# brushed_motor_drivers.net
KiCad netlist of a schematic drawn in Altium Designer
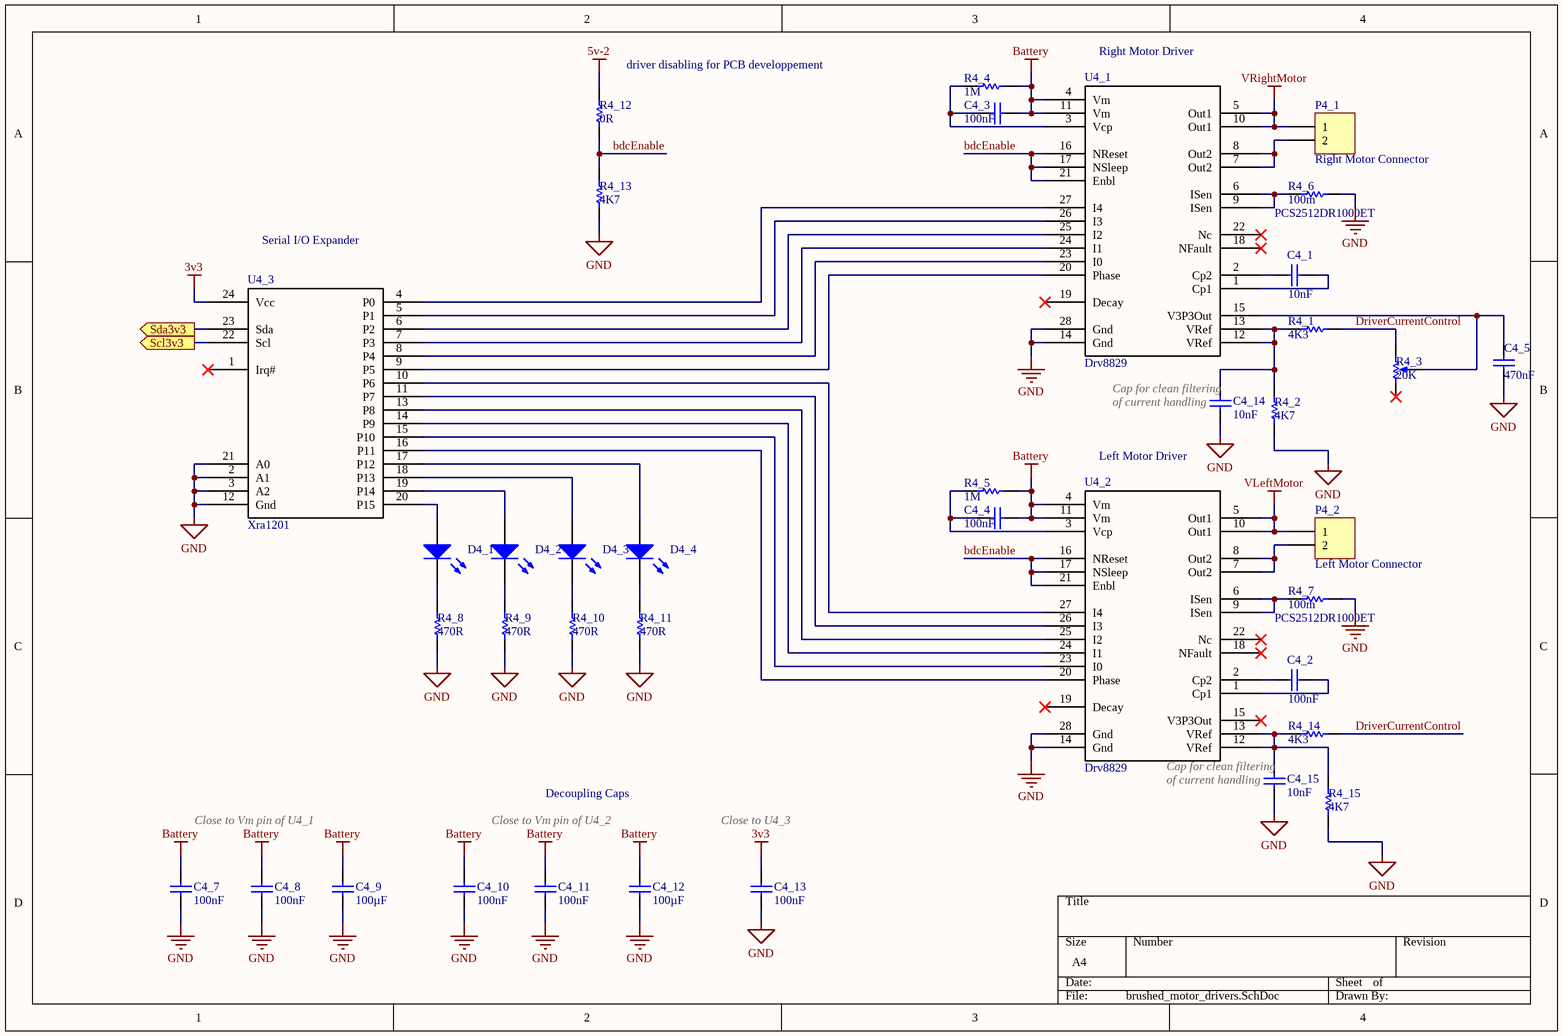
[diagram p0: brushed_motor_drivers.SchDoc]

(export (version "E")
  (design (tool "Eeschema 10.0.6"))
  (components
    (comp (ref "C4_1")
      (value "10nF")
      (footprint "C1206")
      (description "Capacitor")
      (fields (field (name "Comment") "C1206C103M5RACTU") (field (name "PUBLISHER") "Altium Limited"))
      (libsource (lib "Miscellaneous Devices") (part "Cap"))
    )
    (comp (ref "C4_2")
      (value "100nF")
      (footprint "C1206")
      (description "Capacitor")
      (fields (field (name "Comment") "C1206C103M5RACTU") (field (name "PUBLISHER") "Altium Limited"))
      (libsource (lib "Miscellaneous Devices") (part "Cap"))
    )
    (comp (ref "C4_3")
      (value "100nF")
      (footprint "C1206")
      (description "Capacitor")
      (fields (field (name "Comment") "12063C104MAT2A") (field (name "PUBLISHER") "Altium Limited"))
      (libsource (lib "Miscellaneous Devices") (part "Cap"))
    )
    (comp (ref "C4_4")
      (value "100nF")
      (footprint "C1206")
      (description "Capacitor")
      (fields (field (name "Comment") "12063C104MAT2A") (field (name "PUBLISHER") "Altium Limited"))
      (libsource (lib "Miscellaneous Devices") (part "Cap"))
    )
    (comp (ref "C4_5")
      (value "470nF")
      (footprint "C1206")
      (description "Capacitor")
      (fields (field (name "Comment") "C1206C474M5RECAUTO") (field (name "PUBLISHER") "Altium Limited"))
      (libsource (lib "Miscellaneous Devices") (part "Cap"))
    )
    (comp (ref "C4_7")
      (value "100nF")
      (footprint "C1206")
      (description "Capacitor")
      (fields (field (name "Comment") "12063C104MAT2A") (field (name "PUBLISHER") "Altium Limited"))
      (libsource (lib "Miscellaneous Devices") (part "Cap"))
    )
    (comp (ref "C4_8")
      (value "100nF")
      (footprint "C1206")
      (description "Capacitor")
      (fields (field (name "Comment") "12063C104MAT2A") (field (name "PUBLISHER") "Altium Limited"))
      (libsource (lib "Miscellaneous Devices") (part "Cap"))
    )
    (comp (ref "C4_9")
      (value "100µF")
      (footprint "CAP-ELECTRO-530530")
      (description "Capacitor")
      (fields (field (name "Comment") "107AXZ016MQ5") (field (name "PUBLISHER") "Altium Limited"))
      (libsource (lib "Miscellaneous Devices") (part "Cap"))
    )
    (comp (ref "C4_10")
      (value "100nF")
      (footprint "C1206")
      (description "Capacitor")
      (fields (field (name "Comment") "12063C104MAT2A") (field (name "PUBLISHER") "Altium Limited"))
      (libsource (lib "Miscellaneous Devices") (part "Cap"))
    )
    (comp (ref "C4_11")
      (value "100nF")
      (footprint "C1206")
      (description "Capacitor")
      (fields (field (name "Comment") "12063C104MAT2A") (field (name "PUBLISHER") "Altium Limited"))
      (libsource (lib "Miscellaneous Devices") (part "Cap"))
    )
    (comp (ref "C4_12")
      (value "100µF")
      (footprint "CAP-ELECTRO-530530")
      (description "Capacitor")
      (fields (field (name "Comment") "107AXZ016MQ5") (field (name "PUBLISHER") "Altium Limited"))
      (libsource (lib "Miscellaneous Devices") (part "Cap"))
    )
    (comp (ref "C4_13")
      (value "100nF")
      (footprint "C1206")
      (description "Capacitor")
      (fields (field (name "Comment") "12063C104MAT2A") (field (name "PUBLISHER") "Altium Limited"))
      (libsource (lib "Miscellaneous Devices") (part "Cap"))
    )
    (comp (ref "C4_14")
      (value "10nF")
      (footprint "C1206")
      (description "Capacitor")
      (fields (field (name "Comment") "C1206C103M5RACTU") (field (name "PUBLISHER") "Altium Limited"))
      (libsource (lib "Miscellaneous Devices") (part "Cap"))
    )
    (comp (ref "C4_15")
      (value "10nF")
      (footprint "C1206")
      (description "Capacitor")
      (fields (field (name "Comment") "C1206C103M5RACTU") (field (name "PUBLISHER") "Altium Limited"))
      (libsource (lib "Miscellaneous Devices") (part "Cap"))
    )
    (comp (ref "D4_1")
      (value "APT3216QBC/D")
      (footprint "C1206-POLARIZED")
      (description "Typical INFRARED GaAs LED")
      (fields (field (name "PUBLISHER") "Altium Limited"))
      (libsource (lib "Miscellaneous Devices") (part "LED0"))
    )
    (comp (ref "D4_2")
      (value "APT3216QBC/D")
      (footprint "C1206-POLARIZED")
      (description "Typical INFRARED GaAs LED")
      (fields (field (name "PUBLISHER") "Altium Limited"))
      (libsource (lib "Miscellaneous Devices") (part "LED0"))
    )
    (comp (ref "D4_3")
      (value "APT3216QBC/D")
      (footprint "C1206-POLARIZED")
      (description "Typical INFRARED GaAs LED")
      (fields (field (name "PUBLISHER") "Altium Limited"))
      (libsource (lib "Miscellaneous Devices") (part "LED0"))
    )
    (comp (ref "D4_4")
      (value "APT3216QBC/D")
      (footprint "C1206-POLARIZED")
      (description "Typical INFRARED GaAs LED")
      (fields (field (name "PUBLISHER") "Altium Limited"))
      (libsource (lib "Miscellaneous Devices") (part "LED0"))
    )
    (comp (ref "P4_1")
      (value "Right Motor Connector")
      (footprint "HDR1X2-42")
      (description "Header, 2-Pin")
      (fields (field (name "PUBLISHER") "Altium Limited"))
      (libsource (lib "Miscellaneous Connectors") (part "Header 2"))
    )
    (comp (ref "P4_2")
      (value "Left Motor Connector")
      (footprint "HDR1X2-42")
      (description "Header, 2-Pin")
      (fields (field (name "PUBLISHER") "Altium Limited"))
      (libsource (lib "Miscellaneous Connectors") (part "Header 2"))
    )
    (comp (ref "R4_1")
      (value "4K3")
      (footprint "C1206")
      (description "Resistor")
      (fields (field (name "Comment") "Res1") (field (name "PUBLISHER") "Altium Limited"))
      (libsource (lib "Miscellaneous Devices") (part "Res1"))
    )
    (comp (ref "R4_2")
      (value "4K7")
      (footprint "C1206")
      (description "Resistor")
      (fields (field (name "Comment") "Res1") (field (name "PUBLISHER") "Altium Limited"))
      (libsource (lib "Miscellaneous Devices") (part "Res1"))
    )
    (comp (ref "R4_3")
      (value "20K")
      (footprint "ST-32EB")
      (description "Potentiometer")
      (fields (field (name "Comment") "ST32ETB203") (field (name "PUBLISHER") "Altium Limited"))
      (libsource (lib "Miscellaneous Devices") (part "RPot"))
    )
    (comp (ref "R4_4")
      (value "1M")
      (footprint "C1206")
      (description "Resistor")
      (fields (field (name "Comment") "Res1") (field (name "PUBLISHER") "Altium Limited"))
      (libsource (lib "Miscellaneous Devices") (part "Res1"))
    )
    (comp (ref "R4_5")
      (value "1M")
      (footprint "C1206")
      (description "Resistor")
      (fields (field (name "Comment") "Res1") (field (name "PUBLISHER") "Altium Limited"))
      (libsource (lib "Miscellaneous Devices") (part "Res1"))
    )
    (comp (ref "R4_6")
      (value "PCS2512DR1000ET")
      (footprint "2512")
      (description "Resistor")
      (fields (field (name "ALTIUM_VALUE") "100m") (field (name "PUBLISHER") "Altium Limited"))
      (libsource (lib "Miscellaneous Devices") (part "Res1"))
    )
    (comp (ref "R4_7")
      (value "PCS2512DR1000ET")
      (footprint "2512")
      (description "Resistor")
      (fields (field (name "ALTIUM_VALUE") "100m") (field (name "PUBLISHER") "Altium Limited"))
      (libsource (lib "Miscellaneous Devices") (part "Res1"))
    )
    (comp (ref "R4_8")
      (value "470R")
      (footprint "C1206")
      (description "Resistor")
      (fields (field (name "Comment") "Res1") (field (name "PUBLISHER") "Altium Limited"))
      (libsource (lib "Miscellaneous Devices") (part "Res1"))
    )
    (comp (ref "R4_9")
      (value "470R")
      (footprint "C1206")
      (description "Resistor")
      (fields (field (name "Comment") "Res1") (field (name "PUBLISHER") "Altium Limited"))
      (libsource (lib "Miscellaneous Devices") (part "Res1"))
    )
    (comp (ref "R4_10")
      (value "470R")
      (footprint "C1206")
      (description "Resistor")
      (fields (field (name "Comment") "Res1") (field (name "PUBLISHER") "Altium Limited"))
      (libsource (lib "Miscellaneous Devices") (part "Res1"))
    )
    (comp (ref "R4_11")
      (value "470R")
      (footprint "C1206")
      (description "Resistor")
      (fields (field (name "Comment") "Res1") (field (name "PUBLISHER") "Altium Limited"))
      (libsource (lib "Miscellaneous Devices") (part "Res1"))
    )
    (comp (ref "R4_12")
      (value "0R")
      (footprint "C0805")
      (description "Resistor")
      (fields (field (name "Comment") "Res1") (field (name "PUBLISHER") "Altium Limited"))
      (libsource (lib "Miscellaneous Devices") (part "Res1"))
    )
    (comp (ref "R4_13")
      (value "4K7")
      (footprint "C1206")
      (description "Resistor")
      (fields (field (name "Comment") "Res1") (field (name "PUBLISHER") "Altium Limited"))
      (libsource (lib "Miscellaneous Devices") (part "Res1"))
    )
    (comp (ref "R4_14")
      (value "4K3")
      (footprint "C1206")
      (description "Resistor")
      (fields (field (name "Comment") "Res1") (field (name "PUBLISHER") "Altium Limited"))
      (libsource (lib "Miscellaneous Devices") (part "Res1"))
    )
    (comp (ref "R4_15")
      (value "4K7")
      (footprint "C1206")
      (description "Resistor")
      (fields (field (name "Comment") "Res1") (field (name "PUBLISHER") "Altium Limited"))
      (libsource (lib "Miscellaneous Devices") (part "Res1"))
    )
    (comp (ref "U4_1")
      (value "Drv8829")
      (footprint "SOP65P640X120-28N-GROUND_SINK")
      (libsource (lib "projet 6e session") (part "Drv8829"))
    )
    (comp (ref "U4_2")
      (value "Drv8829")
      (footprint "SOP65P640X120-28N-GROUND_SINK")
      (libsource (lib "projet 6e session") (part "Drv8829"))
    )
    (comp (ref "U4_3")
      (value "Xra1201")
      (footprint "SOP65P640X110-24N")
      (libsource (lib "projet 6e session") (part "Xra1201"))
    )
  )
  (nets
    (net (code "1") (name "/DriverCurrentControl") (class "Default")
      (node (ref "R4_1") (pin "2") (pinfunction "2_2") (pintype "passive"))
      (node (ref "R4_14") (pin "2") (pinfunction "2_2") (pintype "passive"))
      (node (ref "R4_3") (pin "2") (pinfunction "BOT_2") (pintype "passive"))
    )
    (net (code "2") (name "/Scl3v3") (class "Default")
      (node (ref "U4_3") (pin "22") (pinfunction "Scl_22") (pintype "passive"))
    )
    (net (code "3") (name "/Sda3v3") (class "Default")
      (node (ref "U4_3") (pin "23") (pinfunction "Sda_23") (pintype "passive"))
    )
    (net (code "4") (name "/bdcEnable") (class "Default")
      (node (ref "R4_12") (pin "2") (pinfunction "2_2") (pintype "passive"))
      (node (ref "R4_13") (pin "1") (pinfunction "1_1") (pintype "passive"))
      (node (ref "U4_1") (pin "16") (pinfunction "NReset_16") (pintype "passive"))
      (node (ref "U4_1") (pin "17") (pinfunction "NSleep_17") (pintype "passive"))
      (node (ref "U4_1") (pin "21") (pinfunction "Enbl_21") (pintype "passive"))
      (node (ref "U4_2") (pin "16") (pinfunction "NReset_16") (pintype "passive"))
      (node (ref "U4_2") (pin "17") (pinfunction "NSleep_17") (pintype "passive"))
      (node (ref "U4_2") (pin "21") (pinfunction "Enbl_21") (pintype "passive"))
    )
    (net (code "5") (name "3v3") (class "Default")
      (node (ref "C4_13") (pin "1") (pinfunction "1_1") (pintype "passive"))
      (node (ref "U4_3") (pin "24") (pinfunction "Vcc_24") (pintype "passive"))
    )
    (net (code "6") (name "5v-2") (class "Default")
      (node (ref "R4_12") (pin "1") (pinfunction "1_1") (pintype "passive"))
    )
    (net (code "7") (name "Battery") (class "Default")
      (node (ref "C4_10") (pin "1") (pinfunction "1_1") (pintype "passive"))
      (node (ref "C4_11") (pin "1") (pinfunction "1_1") (pintype "passive"))
      (node (ref "C4_12") (pin "1") (pinfunction "1_1") (pintype "passive"))
      (node (ref "C4_3") (pin "1") (pinfunction "1_1") (pintype "passive"))
      (node (ref "C4_4") (pin "1") (pinfunction "1_1") (pintype "passive"))
      (node (ref "C4_7") (pin "1") (pinfunction "1_1") (pintype "passive"))
      (node (ref "C4_8") (pin "1") (pinfunction "1_1") (pintype "passive"))
      (node (ref "C4_9") (pin "1") (pinfunction "1_1") (pintype "passive"))
      (node (ref "R4_4") (pin "2") (pinfunction "2_2") (pintype "passive"))
      (node (ref "R4_5") (pin "2") (pinfunction "2_2") (pintype "passive"))
      (node (ref "U4_1") (pin "11") (pinfunction "Vm_11") (pintype "passive"))
      (node (ref "U4_1") (pin "4") (pinfunction "Vm_4") (pintype "passive"))
      (node (ref "U4_2") (pin "11") (pinfunction "Vm_11") (pintype "passive"))
      (node (ref "U4_2") (pin "4") (pinfunction "Vm_4") (pintype "passive"))
    )
    (net (code "8") (name "GND") (class "Default")
      (node (ref "C4_10") (pin "2") (pinfunction "2_2") (pintype "passive"))
      (node (ref "C4_11") (pin "2") (pinfunction "2_2") (pintype "passive"))
      (node (ref "C4_12") (pin "2") (pinfunction "2_2") (pintype "passive"))
      (node (ref "C4_13") (pin "2") (pinfunction "2_2") (pintype "passive"))
      (node (ref "C4_14") (pin "2") (pinfunction "2_2") (pintype "passive"))
      (node (ref "C4_15") (pin "2") (pinfunction "2_2") (pintype "passive"))
      (node (ref "C4_5") (pin "2") (pinfunction "2_2") (pintype "passive"))
      (node (ref "C4_7") (pin "2") (pinfunction "2_2") (pintype "passive"))
      (node (ref "C4_8") (pin "2") (pinfunction "2_2") (pintype "passive"))
      (node (ref "C4_9") (pin "2") (pinfunction "2_2") (pintype "passive"))
      (node (ref "R4_10") (pin "2") (pinfunction "2_2") (pintype "passive"))
      (node (ref "R4_11") (pin "2") (pinfunction "2_2") (pintype "passive"))
      (node (ref "R4_13") (pin "2") (pinfunction "2_2") (pintype "passive"))
      (node (ref "R4_15") (pin "2") (pinfunction "2_2") (pintype "passive"))
      (node (ref "R4_2") (pin "2") (pinfunction "2_2") (pintype "passive"))
      (node (ref "R4_6") (pin "2") (pinfunction "2_2") (pintype "passive"))
      (node (ref "R4_7") (pin "2") (pinfunction "2_2") (pintype "passive"))
      (node (ref "R4_8") (pin "2") (pinfunction "2_2") (pintype "passive"))
      (node (ref "R4_9") (pin "2") (pinfunction "2_2") (pintype "passive"))
      (node (ref "U4_1") (pin "14") (pinfunction "Gnd_14") (pintype "passive"))
      (node (ref "U4_1") (pin "28") (pinfunction "Gnd_28") (pintype "passive"))
      (node (ref "U4_2") (pin "14") (pinfunction "Gnd_14") (pintype "passive"))
      (node (ref "U4_2") (pin "28") (pinfunction "Gnd_28") (pintype "passive"))
      (node (ref "U4_3") (pin "12") (pinfunction "Gnd_12") (pintype "passive"))
      (node (ref "U4_3") (pin "2") (pinfunction "A1_2") (pintype "passive"))
      (node (ref "U4_3") (pin "21") (pinfunction "A0_21") (pintype "passive"))
      (node (ref "U4_3") (pin "3") (pinfunction "A2_3") (pintype "passive"))
    )
    (net (code "9") (name "Net-(C4_14-Pad1)") (class "Default")
      (node (ref "C4_14") (pin "1") (pinfunction "1_1") (pintype "passive"))
      (node (ref "R4_1") (pin "1") (pinfunction "1_1") (pintype "passive"))
      (node (ref "R4_2") (pin "1") (pinfunction "1_1") (pintype "passive"))
      (node (ref "U4_1") (pin "12") (pinfunction "VRef_12") (pintype "passive"))
      (node (ref "U4_1") (pin "13") (pinfunction "VRef_13") (pintype "passive"))
    )
    (net (code "10") (name "Net-(C4_15-Pad1)") (class "Default")
      (node (ref "C4_15") (pin "1") (pinfunction "1_1") (pintype "passive"))
      (node (ref "R4_14") (pin "1") (pinfunction "1_1") (pintype "passive"))
      (node (ref "R4_15") (pin "1") (pinfunction "1_1") (pintype "passive"))
      (node (ref "U4_2") (pin "12") (pinfunction "VRef_12") (pintype "passive"))
      (node (ref "U4_2") (pin "13") (pinfunction "VRef_13") (pintype "passive"))
    )
    (net (code "11") (name "Net-(D4_1-A)") (class "Default")
      (node (ref "D4_1") (pin "1") (pinfunction "A_1") (pintype "passive"))
      (node (ref "U4_3") (pin "20") (pinfunction "P15_20") (pintype "passive"))
    )
    (net (code "12") (name "Net-(D4_1-K)") (class "Default")
      (node (ref "D4_1") (pin "2") (pinfunction "K_2") (pintype "passive"))
      (node (ref "R4_8") (pin "1") (pinfunction "1_1") (pintype "passive"))
    )
    (net (code "13") (name "Net-(D4_2-A)") (class "Default")
      (node (ref "D4_2") (pin "1") (pinfunction "A_1") (pintype "passive"))
      (node (ref "U4_3") (pin "19") (pinfunction "P14_19") (pintype "passive"))
    )
    (net (code "14") (name "Net-(D4_2-K)") (class "Default")
      (node (ref "D4_2") (pin "2") (pinfunction "K_2") (pintype "passive"))
      (node (ref "R4_9") (pin "1") (pinfunction "1_1") (pintype "passive"))
    )
    (net (code "15") (name "Net-(D4_3-A)") (class "Default")
      (node (ref "D4_3") (pin "1") (pinfunction "A_1") (pintype "passive"))
      (node (ref "U4_3") (pin "18") (pinfunction "P13_18") (pintype "passive"))
    )
    (net (code "16") (name "Net-(D4_3-K)") (class "Default")
      (node (ref "D4_3") (pin "2") (pinfunction "K_2") (pintype "passive"))
      (node (ref "R4_10") (pin "1") (pinfunction "1_1") (pintype "passive"))
    )
    (net (code "17") (name "Net-(D4_4-A)") (class "Default")
      (node (ref "D4_4") (pin "1") (pinfunction "A_1") (pintype "passive"))
      (node (ref "U4_3") (pin "17") (pinfunction "P12_17") (pintype "passive"))
    )
    (net (code "18") (name "Net-(D4_4-K)") (class "Default")
      (node (ref "D4_4") (pin "2") (pinfunction "K_2") (pintype "passive"))
      (node (ref "R4_11") (pin "1") (pinfunction "1_1") (pintype "passive"))
    )
    (net (code "19") (name "Net-(P4_1-Pad2)") (class "Default")
      (node (ref "P4_1") (pin "2") (pinfunction "2_2") (pintype "passive"))
      (node (ref "U4_1") (pin "7") (pinfunction "Out2_7") (pintype "passive"))
      (node (ref "U4_1") (pin "8") (pinfunction "Out2_8") (pintype "passive"))
    )
    (net (code "20") (name "Net-(P4_2-Pad2)") (class "Default")
      (node (ref "P4_2") (pin "2") (pinfunction "2_2") (pintype "passive"))
      (node (ref "U4_2") (pin "7") (pinfunction "Out2_7") (pintype "passive"))
      (node (ref "U4_2") (pin "8") (pinfunction "Out2_8") (pintype "passive"))
    )
    (net (code "21") (name "Net-(R4_3-TAP)") (class "Default")
      (node (ref "C4_5") (pin "1") (pinfunction "1_1") (pintype "passive"))
      (node (ref "R4_3") (pin "3") (pinfunction "TAP_3") (pintype "passive"))
      (node (ref "U4_1") (pin "15") (pinfunction "V3P3Out_15") (pintype "passive"))
    )
    (net (code "22") (name "Net-(R4_6-Pad1)") (class "Default")
      (node (ref "R4_6") (pin "1") (pinfunction "1_1") (pintype "passive"))
      (node (ref "U4_1") (pin "6") (pinfunction "ISen_6") (pintype "passive"))
      (node (ref "U4_1") (pin "9") (pinfunction "ISen_9") (pintype "passive"))
    )
    (net (code "23") (name "Net-(R4_7-Pad1)") (class "Default")
      (node (ref "R4_7") (pin "1") (pinfunction "1_1") (pintype "passive"))
      (node (ref "U4_2") (pin "6") (pinfunction "ISen_6") (pintype "passive"))
      (node (ref "U4_2") (pin "9") (pinfunction "ISen_9") (pintype "passive"))
    )
    (net (code "24") (name "Net-(U4_1-Cp1)") (class "Default")
      (node (ref "C4_1") (pin "1") (pinfunction "1_1") (pintype "passive"))
      (node (ref "U4_1") (pin "1") (pinfunction "Cp1_1") (pintype "passive"))
    )
    (net (code "25") (name "Net-(U4_1-Cp2)") (class "Default")
      (node (ref "C4_1") (pin "2") (pinfunction "2_2") (pintype "passive"))
      (node (ref "U4_1") (pin "2") (pinfunction "Cp2_2") (pintype "passive"))
    )
    (net (code "26") (name "Net-(U4_1-I0)") (class "Default")
      (node (ref "U4_1") (pin "23") (pinfunction "I0_23") (pintype "passive"))
      (node (ref "U4_3") (pin "8") (pinfunction "P4_8") (pintype "passive"))
    )
    (net (code "27") (name "Net-(U4_1-I1)") (class "Default")
      (node (ref "U4_1") (pin "24") (pinfunction "I1_24") (pintype "passive"))
      (node (ref "U4_3") (pin "7") (pinfunction "P3_7") (pintype "passive"))
    )
    (net (code "28") (name "Net-(U4_1-I2)") (class "Default")
      (node (ref "U4_1") (pin "25") (pinfunction "I2_25") (pintype "passive"))
      (node (ref "U4_3") (pin "6") (pinfunction "P2_6") (pintype "passive"))
    )
    (net (code "29") (name "Net-(U4_1-I3)") (class "Default")
      (node (ref "U4_1") (pin "26") (pinfunction "I3_26") (pintype "passive"))
      (node (ref "U4_3") (pin "5") (pinfunction "P1_5") (pintype "passive"))
    )
    (net (code "30") (name "Net-(U4_1-I4)") (class "Default")
      (node (ref "U4_1") (pin "27") (pinfunction "I4_27") (pintype "passive"))
      (node (ref "U4_3") (pin "4") (pinfunction "P0_4") (pintype "passive"))
    )
    (net (code "31") (name "Net-(U4_1-Phase)") (class "Default")
      (node (ref "U4_1") (pin "20") (pinfunction "Phase_20") (pintype "passive"))
      (node (ref "U4_3") (pin "9") (pinfunction "P5_9") (pintype "passive"))
    )
    (net (code "32") (name "Net-(U4_1-Vcp)") (class "Default")
      (node (ref "C4_3") (pin "2") (pinfunction "2_2") (pintype "passive"))
      (node (ref "R4_4") (pin "1") (pinfunction "1_1") (pintype "passive"))
      (node (ref "U4_1") (pin "3") (pinfunction "Vcp_3") (pintype "passive"))
    )
    (net (code "33") (name "Net-(U4_2-Cp1)") (class "Default")
      (node (ref "C4_2") (pin "1") (pinfunction "1_1") (pintype "passive"))
      (node (ref "U4_2") (pin "1") (pinfunction "Cp1_1") (pintype "passive"))
    )
    (net (code "34") (name "Net-(U4_2-Cp2)") (class "Default")
      (node (ref "C4_2") (pin "2") (pinfunction "2_2") (pintype "passive"))
      (node (ref "U4_2") (pin "2") (pinfunction "Cp2_2") (pintype "passive"))
    )
    (net (code "35") (name "Net-(U4_2-I0)") (class "Default")
      (node (ref "U4_2") (pin "23") (pinfunction "I0_23") (pintype "passive"))
      (node (ref "U4_3") (pin "15") (pinfunction "P10_15") (pintype "passive"))
    )
    (net (code "36") (name "Net-(U4_2-I1)") (class "Default")
      (node (ref "U4_2") (pin "24") (pinfunction "I1_24") (pintype "passive"))
      (node (ref "U4_3") (pin "14") (pinfunction "P9_14") (pintype "passive"))
    )
    (net (code "37") (name "Net-(U4_2-I2)") (class "Default")
      (node (ref "U4_2") (pin "25") (pinfunction "I2_25") (pintype "passive"))
      (node (ref "U4_3") (pin "13") (pinfunction "P8_13") (pintype "passive"))
    )
    (net (code "38") (name "Net-(U4_2-I3)") (class "Default")
      (node (ref "U4_2") (pin "26") (pinfunction "I3_26") (pintype "passive"))
      (node (ref "U4_3") (pin "11") (pinfunction "P7_11") (pintype "passive"))
    )
    (net (code "39") (name "Net-(U4_2-I4)") (class "Default")
      (node (ref "U4_2") (pin "27") (pinfunction "I4_27") (pintype "passive"))
      (node (ref "U4_3") (pin "10") (pinfunction "P6_10") (pintype "passive"))
    )
    (net (code "40") (name "Net-(U4_2-Phase)") (class "Default")
      (node (ref "U4_2") (pin "20") (pinfunction "Phase_20") (pintype "passive"))
      (node (ref "U4_3") (pin "16") (pinfunction "P11_16") (pintype "passive"))
    )
    (net (code "41") (name "Net-(U4_2-Vcp)") (class "Default")
      (node (ref "C4_4") (pin "2") (pinfunction "2_2") (pintype "passive"))
      (node (ref "R4_5") (pin "1") (pinfunction "1_1") (pintype "passive"))
      (node (ref "U4_2") (pin "3") (pinfunction "Vcp_3") (pintype "passive"))
    )
    (net (code "42") (name "VLeftMotor") (class "Default")
      (node (ref "P4_2") (pin "1") (pinfunction "1_1") (pintype "passive"))
      (node (ref "U4_2") (pin "10") (pinfunction "Out1_10") (pintype "passive"))
      (node (ref "U4_2") (pin "5") (pinfunction "Out1_5") (pintype "passive"))
    )
    (net (code "43") (name "VRightMotor") (class "Default")
      (node (ref "P4_1") (pin "1") (pinfunction "1_1") (pintype "passive"))
      (node (ref "U4_1") (pin "10") (pinfunction "Out1_10") (pintype "passive"))
      (node (ref "U4_1") (pin "5") (pinfunction "Out1_5") (pintype "passive"))
    )
    (net (code "44") (name "unconnected-(R4_3-TOP-Pad1)") (class "Default")
      (node (ref "R4_3") (pin "1") (pinfunction "TOP_1") (pintype "passive+no_connect"))
    )
    (net (code "45") (name "unconnected-(U4_1-Decay-Pad19)") (class "Default")
      (node (ref "U4_1") (pin "19") (pinfunction "Decay_19") (pintype "passive+no_connect"))
    )
    (net (code "46") (name "unconnected-(U4_1-NFault-Pad18)") (class "Default")
      (node (ref "U4_1") (pin "18") (pinfunction "NFault_18") (pintype "passive+no_connect"))
    )
    (net (code "47") (name "unconnected-(U4_1-Nc-Pad22)") (class "Default")
      (node (ref "U4_1") (pin "22") (pinfunction "Nc_22") (pintype "passive+no_connect"))
    )
    (net (code "48") (name "unconnected-(U4_2-Decay-Pad19)") (class "Default")
      (node (ref "U4_2") (pin "19") (pinfunction "Decay_19") (pintype "passive+no_connect"))
    )
    (net (code "49") (name "unconnected-(U4_2-NFault-Pad18)") (class "Default")
      (node (ref "U4_2") (pin "18") (pinfunction "NFault_18") (pintype "passive+no_connect"))
    )
    (net (code "50") (name "unconnected-(U4_2-Nc-Pad22)") (class "Default")
      (node (ref "U4_2") (pin "22") (pinfunction "Nc_22") (pintype "passive+no_connect"))
    )
    (net (code "51") (name "unconnected-(U4_2-V3P3Out-Pad15)") (class "Default")
      (node (ref "U4_2") (pin "15") (pinfunction "V3P3Out_15") (pintype "passive+no_connect"))
    )
    (net (code "52") (name "unconnected-(U4_3-Irq#-Pad1)") (class "Default")
      (node (ref "U4_3") (pin "1") (pinfunction "Irq#_1") (pintype "passive+no_connect"))
    )
  )
)
